# address_decoder_v1.net
KiCad netlist of a schematic drawn in EAGLE
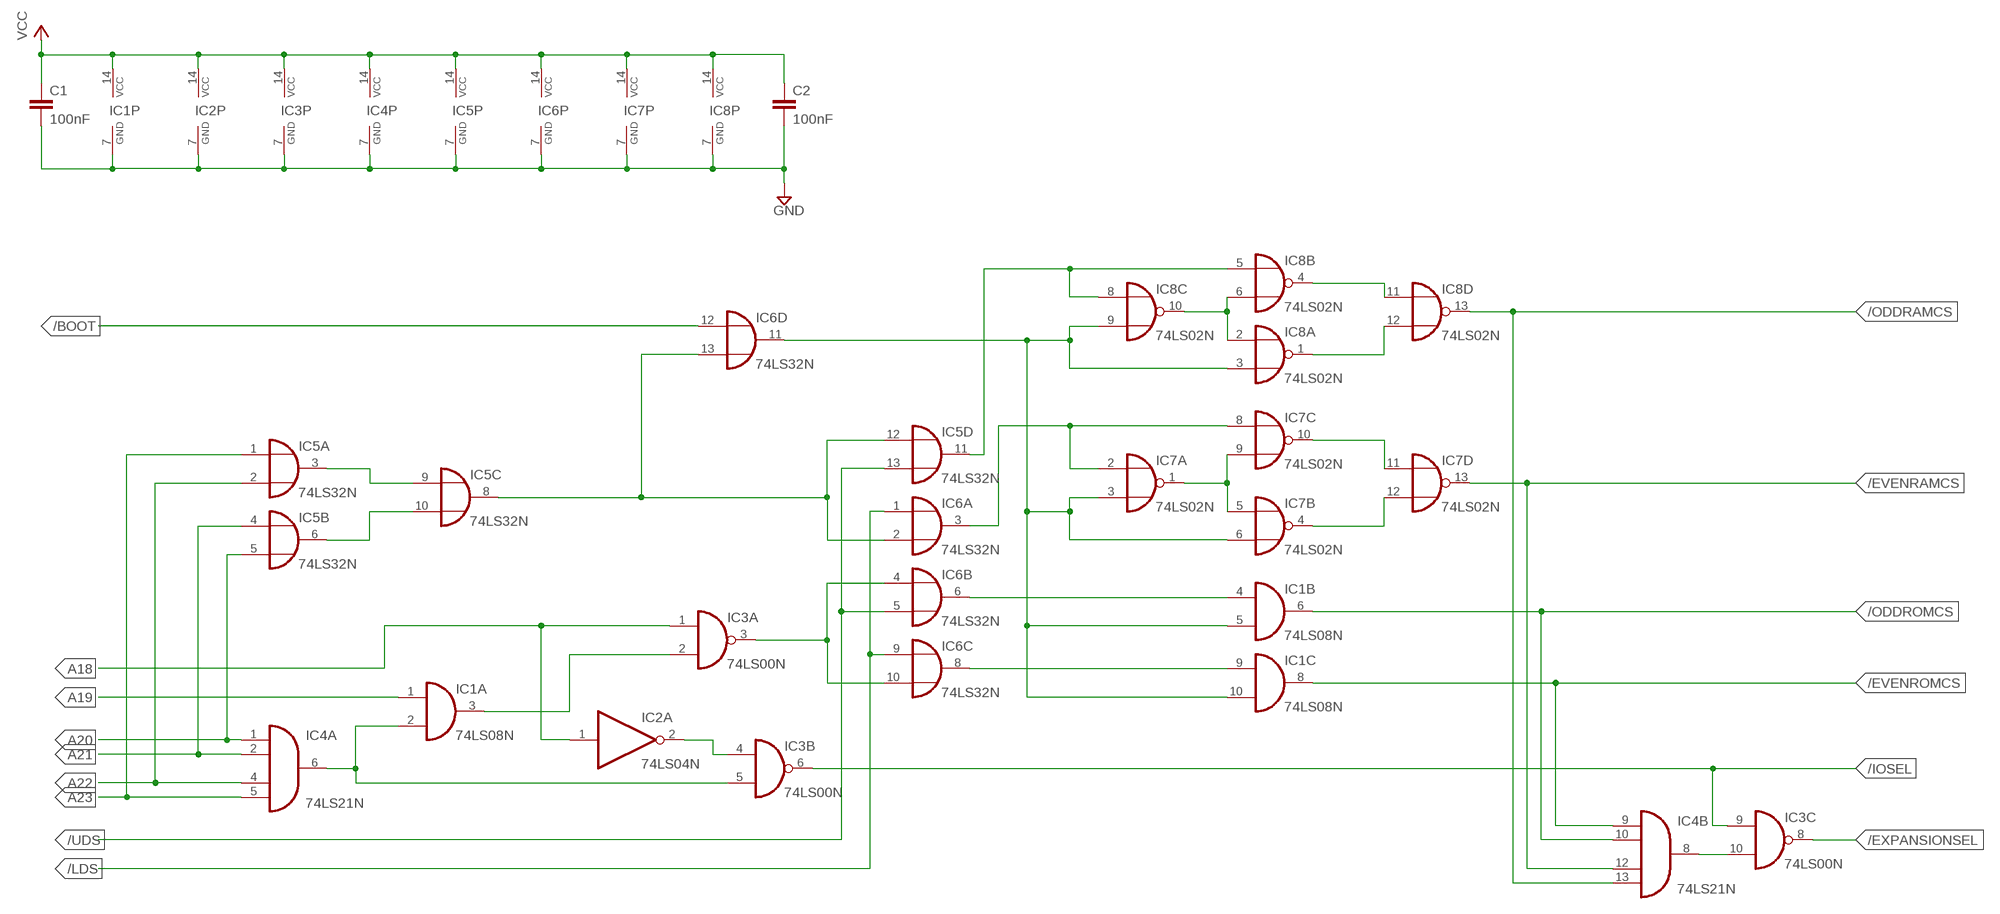
[diagram p0: schematic, sheet 1]

(export (version "E")
  (design (tool "Eeschema 10.0.6"))
  (components
    (comp (ref "C1")
      (value "100nF")
      (footprint "eagle-import:C025-024X044")
      (libsource (lib "eagle-import") (part "C-EU025-024X044"))
    )
    (comp (ref "C2")
      (value "100nF")
      (footprint "eagle-import:C025-024X044")
      (libsource (lib "eagle-import") (part "C-EU025-024X044"))
    )
    (comp (ref "IC1")
      (value "74LS08N")
      (footprint "eagle-import:DIL14")
      (libsource (lib "eagle-import") (part "7408NLS"))
    )
    (comp (ref "IC2")
      (value "74LS04N")
      (footprint "eagle-import:DIL14")
      (libsource (lib "eagle-import") (part "7404NLS"))
    )
    (comp (ref "IC3")
      (value "74LS00N")
      (footprint "eagle-import:DIL14")
      (libsource (lib "eagle-import") (part "7400NLS"))
    )
    (comp (ref "IC4")
      (value "74LS21N")
      (footprint "eagle-import:DIL14")
      (libsource (lib "eagle-import") (part "7421NLS"))
    )
    (comp (ref "IC5")
      (value "74LS32N")
      (footprint "eagle-import:DIL14")
      (libsource (lib "eagle-import") (part "7432NLS"))
    )
    (comp (ref "IC6")
      (value "74LS32N")
      (footprint "eagle-import:DIL14")
      (libsource (lib "eagle-import") (part "7432NLS"))
    )
    (comp (ref "IC7")
      (value "74LS02N")
      (footprint "eagle-import:DIL14")
      (libsource (lib "eagle-import") (part "7402NLS"))
    )
    (comp (ref "IC8")
      (value "74LS02N")
      (footprint "eagle-import:DIL14")
      (libsource (lib "eagle-import") (part "7402NLS"))
    )
  )
  (nets
    (net (code "1") (name "A18") (class "Default")
      (node (ref "IC2") (pin "1") (pinfunction "I_1") (pintype "input"))
      (node (ref "IC3") (pin "1") (pinfunction "I0_1") (pintype "input"))
    )
    (net (code "2") (name "A19") (class "Default")
      (node (ref "IC1") (pin "1") (pinfunction "I0_1") (pintype "input"))
    )
    (net (code "3") (name "A20") (class "Default")
      (node (ref "IC4") (pin "1") (pinfunction "I0_1") (pintype "input"))
      (node (ref "IC5") (pin "5") (pinfunction "I1_5") (pintype "input"))
    )
    (net (code "4") (name "A21") (class "Default")
      (node (ref "IC4") (pin "2") (pinfunction "I1_2") (pintype "input"))
      (node (ref "IC5") (pin "4") (pinfunction "I0_4") (pintype "input"))
    )
    (net (code "5") (name "A22") (class "Default")
      (node (ref "IC4") (pin "4") (pinfunction "I2_4") (pintype "input"))
      (node (ref "IC5") (pin "2") (pinfunction "I1_2") (pintype "input"))
    )
    (net (code "6") (name "A23") (class "Default")
      (node (ref "IC4") (pin "5") (pinfunction "I3_5") (pintype "input"))
      (node (ref "IC5") (pin "1") (pinfunction "I0_1") (pintype "input"))
    )
    (net (code "7") (name "GND") (class "Default")
      (node (ref "C1") (pin "2") (pinfunction "2_2") (pintype "passive"))
      (node (ref "C2") (pin "2") (pinfunction "2_2") (pintype "passive"))
      (node (ref "IC1") (pin "7") (pinfunction "GND_7") (pintype "power_in"))
      (node (ref "IC2") (pin "7") (pinfunction "GND_7") (pintype "power_in"))
      (node (ref "IC3") (pin "7") (pinfunction "GND_7") (pintype "power_in"))
      (node (ref "IC4") (pin "7") (pinfunction "GND_7") (pintype "power_in"))
      (node (ref "IC5") (pin "7") (pinfunction "GND_7") (pintype "power_in"))
      (node (ref "IC6") (pin "7") (pinfunction "GND_7") (pintype "power_in"))
      (node (ref "IC7") (pin "7") (pinfunction "GND_7") (pintype "power_in"))
      (node (ref "IC8") (pin "7") (pinfunction "GND_7") (pintype "power_in"))
    )
    (net (code "8") (name "Net-(IC1A-I1)") (class "Default")
      (node (ref "IC1") (pin "2") (pinfunction "I1_2") (pintype "input"))
      (node (ref "IC3") (pin "5") (pinfunction "I1_5") (pintype "input"))
      (node (ref "IC4") (pin "6") (pinfunction "O_6") (pintype "output"))
    )
    (net (code "9") (name "Net-(IC1A-O)") (class "Default")
      (node (ref "IC1") (pin "3") (pinfunction "O_3") (pintype "output"))
      (node (ref "IC3") (pin "2") (pinfunction "I1_2") (pintype "input"))
    )
    (net (code "10") (name "Net-(IC1B-I0)") (class "Default")
      (node (ref "IC1") (pin "4") (pinfunction "I0_4") (pintype "input"))
      (node (ref "IC6") (pin "6") (pinfunction "O_6") (pintype "output"))
    )
    (net (code "11") (name "Net-(IC1B-I1)") (class "Default")
      (node (ref "IC1") (pin "10") (pinfunction "I1_10") (pintype "input"))
      (node (ref "IC1") (pin "5") (pinfunction "I1_5") (pintype "input"))
      (node (ref "IC6") (pin "11") (pinfunction "O_11") (pintype "output"))
      (node (ref "IC7") (pin "3") (pinfunction "I1_3") (pintype "input"))
      (node (ref "IC7") (pin "6") (pinfunction "I1_6") (pintype "input"))
      (node (ref "IC8") (pin "3") (pinfunction "I1_3") (pintype "input"))
      (node (ref "IC8") (pin "9") (pinfunction "I1_9") (pintype "input"))
    )
    (net (code "12") (name "Net-(IC1C-I0)") (class "Default")
      (node (ref "IC1") (pin "9") (pinfunction "I0_9") (pintype "input"))
      (node (ref "IC6") (pin "8") (pinfunction "O_8") (pintype "output"))
    )
    (net (code "13") (name "Net-(IC2A-O)") (class "Default")
      (node (ref "IC2") (pin "2") (pinfunction "O_2") (pintype "output"))
      (node (ref "IC3") (pin "4") (pinfunction "I0_4") (pintype "input"))
    )
    (net (code "14") (name "Net-(IC3A-O)") (class "Default")
      (node (ref "IC3") (pin "3") (pinfunction "O_3") (pintype "output"))
      (node (ref "IC6") (pin "10") (pinfunction "I1_10") (pintype "input"))
      (node (ref "IC6") (pin "4") (pinfunction "I0_4") (pintype "input"))
    )
    (net (code "15") (name "Net-(IC3C-I1)") (class "Default")
      (node (ref "IC3") (pin "10") (pinfunction "I1_10") (pintype "input"))
      (node (ref "IC4") (pin "8") (pinfunction "O_8") (pintype "output"))
    )
    (net (code "16") (name "Net-(IC5A-O)") (class "Default")
      (node (ref "IC5") (pin "3") (pinfunction "O_3") (pintype "output"))
      (node (ref "IC5") (pin "9") (pinfunction "I0_9") (pintype "input"))
    )
    (net (code "17") (name "Net-(IC5B-O)") (class "Default")
      (node (ref "IC5") (pin "10") (pinfunction "I1_10") (pintype "input"))
      (node (ref "IC5") (pin "6") (pinfunction "O_6") (pintype "output"))
    )
    (net (code "18") (name "Net-(IC5C-O)") (class "Default")
      (node (ref "IC5") (pin "12") (pinfunction "I0_12") (pintype "input"))
      (node (ref "IC5") (pin "8") (pinfunction "O_8") (pintype "output"))
      (node (ref "IC6") (pin "13") (pinfunction "I1_13") (pintype "input"))
      (node (ref "IC6") (pin "2") (pinfunction "I1_2") (pintype "input"))
    )
    (net (code "19") (name "Net-(IC5D-O)") (class "Default")
      (node (ref "IC5") (pin "11") (pinfunction "O_11") (pintype "output"))
      (node (ref "IC8") (pin "5") (pinfunction "I0_5") (pintype "input"))
      (node (ref "IC8") (pin "8") (pinfunction "I0_8") (pintype "input"))
    )
    (net (code "20") (name "Net-(IC6A-O)") (class "Default")
      (node (ref "IC6") (pin "3") (pinfunction "O_3") (pintype "output"))
      (node (ref "IC7") (pin "2") (pinfunction "I0_2") (pintype "input"))
      (node (ref "IC7") (pin "8") (pinfunction "I0_8") (pintype "input"))
    )
    (net (code "21") (name "Net-(IC7A-O)") (class "Default")
      (node (ref "IC7") (pin "1") (pinfunction "O_1") (pintype "output"))
      (node (ref "IC7") (pin "5") (pinfunction "I0_5") (pintype "input"))
      (node (ref "IC7") (pin "9") (pinfunction "I1_9") (pintype "input"))
    )
    (net (code "22") (name "Net-(IC7B-O)") (class "Default")
      (node (ref "IC7") (pin "12") (pinfunction "I1_12") (pintype "input"))
      (node (ref "IC7") (pin "4") (pinfunction "O_4") (pintype "output"))
    )
    (net (code "23") (name "Net-(IC7C-O)") (class "Default")
      (node (ref "IC7") (pin "10") (pinfunction "O_10") (pintype "output"))
      (node (ref "IC7") (pin "11") (pinfunction "I0_11") (pintype "input"))
    )
    (net (code "24") (name "Net-(IC8A-I0)") (class "Default")
      (node (ref "IC8") (pin "10") (pinfunction "O_10") (pintype "output"))
      (node (ref "IC8") (pin "2") (pinfunction "I0_2") (pintype "input"))
      (node (ref "IC8") (pin "6") (pinfunction "I1_6") (pintype "input"))
    )
    (net (code "25") (name "Net-(IC8A-O)") (class "Default")
      (node (ref "IC8") (pin "1") (pinfunction "O_1") (pintype "output"))
      (node (ref "IC8") (pin "12") (pinfunction "I1_12") (pintype "input"))
    )
    (net (code "26") (name "Net-(IC8B-O)") (class "Default")
      (node (ref "IC8") (pin "11") (pinfunction "I0_11") (pintype "input"))
      (node (ref "IC8") (pin "4") (pinfunction "O_4") (pintype "output"))
    )
    (net (code "27") (name "VCC") (class "Default")
      (node (ref "C1") (pin "1") (pinfunction "1_1") (pintype "passive"))
      (node (ref "C2") (pin "1") (pinfunction "1_1") (pintype "passive"))
      (node (ref "IC1") (pin "14") (pinfunction "VCC_14") (pintype "power_in"))
      (node (ref "IC2") (pin "14") (pinfunction "VCC_14") (pintype "power_in"))
      (node (ref "IC3") (pin "14") (pinfunction "VCC_14") (pintype "power_in"))
      (node (ref "IC4") (pin "14") (pinfunction "VCC_14") (pintype "power_in"))
      (node (ref "IC5") (pin "14") (pinfunction "VCC_14") (pintype "power_in"))
      (node (ref "IC6") (pin "14") (pinfunction "VCC_14") (pintype "power_in"))
      (node (ref "IC7") (pin "14") (pinfunction "VCC_14") (pintype "power_in"))
      (node (ref "IC8") (pin "14") (pinfunction "VCC_14") (pintype "power_in"))
    )
    (net (code "28") (name "{slash}BOOT") (class "Default")
      (node (ref "IC6") (pin "12") (pinfunction "I0_12") (pintype "input"))
    )
    (net (code "29") (name "{slash}EVENRAMCS") (class "Default")
      (node (ref "IC4") (pin "12") (pinfunction "I2_12") (pintype "input"))
      (node (ref "IC7") (pin "13") (pinfunction "O_13") (pintype "output"))
    )
    (net (code "30") (name "{slash}EVENROMCS") (class "Default")
      (node (ref "IC1") (pin "8") (pinfunction "O_8") (pintype "output"))
      (node (ref "IC4") (pin "9") (pinfunction "I0_9") (pintype "input"))
    )
    (net (code "31") (name "{slash}EXPANSIONSEL") (class "Default")
      (node (ref "IC3") (pin "8") (pinfunction "O_8") (pintype "output"))
    )
    (net (code "32") (name "{slash}IOSEL") (class "Default")
      (node (ref "IC3") (pin "6") (pinfunction "O_6") (pintype "output"))
      (node (ref "IC3") (pin "9") (pinfunction "I0_9") (pintype "input"))
    )
    (net (code "33") (name "{slash}LDS") (class "Default")
      (node (ref "IC6") (pin "1") (pinfunction "I0_1") (pintype "input"))
      (node (ref "IC6") (pin "9") (pinfunction "I0_9") (pintype "input"))
    )
    (net (code "34") (name "{slash}ODDRAMCS") (class "Default")
      (node (ref "IC4") (pin "13") (pinfunction "I3_13") (pintype "input"))
      (node (ref "IC8") (pin "13") (pinfunction "O_13") (pintype "output"))
    )
    (net (code "35") (name "{slash}ODDROMCS") (class "Default")
      (node (ref "IC1") (pin "6") (pinfunction "O_6") (pintype "output"))
      (node (ref "IC4") (pin "10") (pinfunction "I1_10") (pintype "input"))
    )
    (net (code "36") (name "{slash}UDS") (class "Default")
      (node (ref "IC5") (pin "13") (pinfunction "I1_13") (pintype "input"))
      (node (ref "IC6") (pin "5") (pinfunction "I1_5") (pintype "input"))
    )
  )
)
